# main.net
KiCad netlist of a schematic drawn in Altium Designer
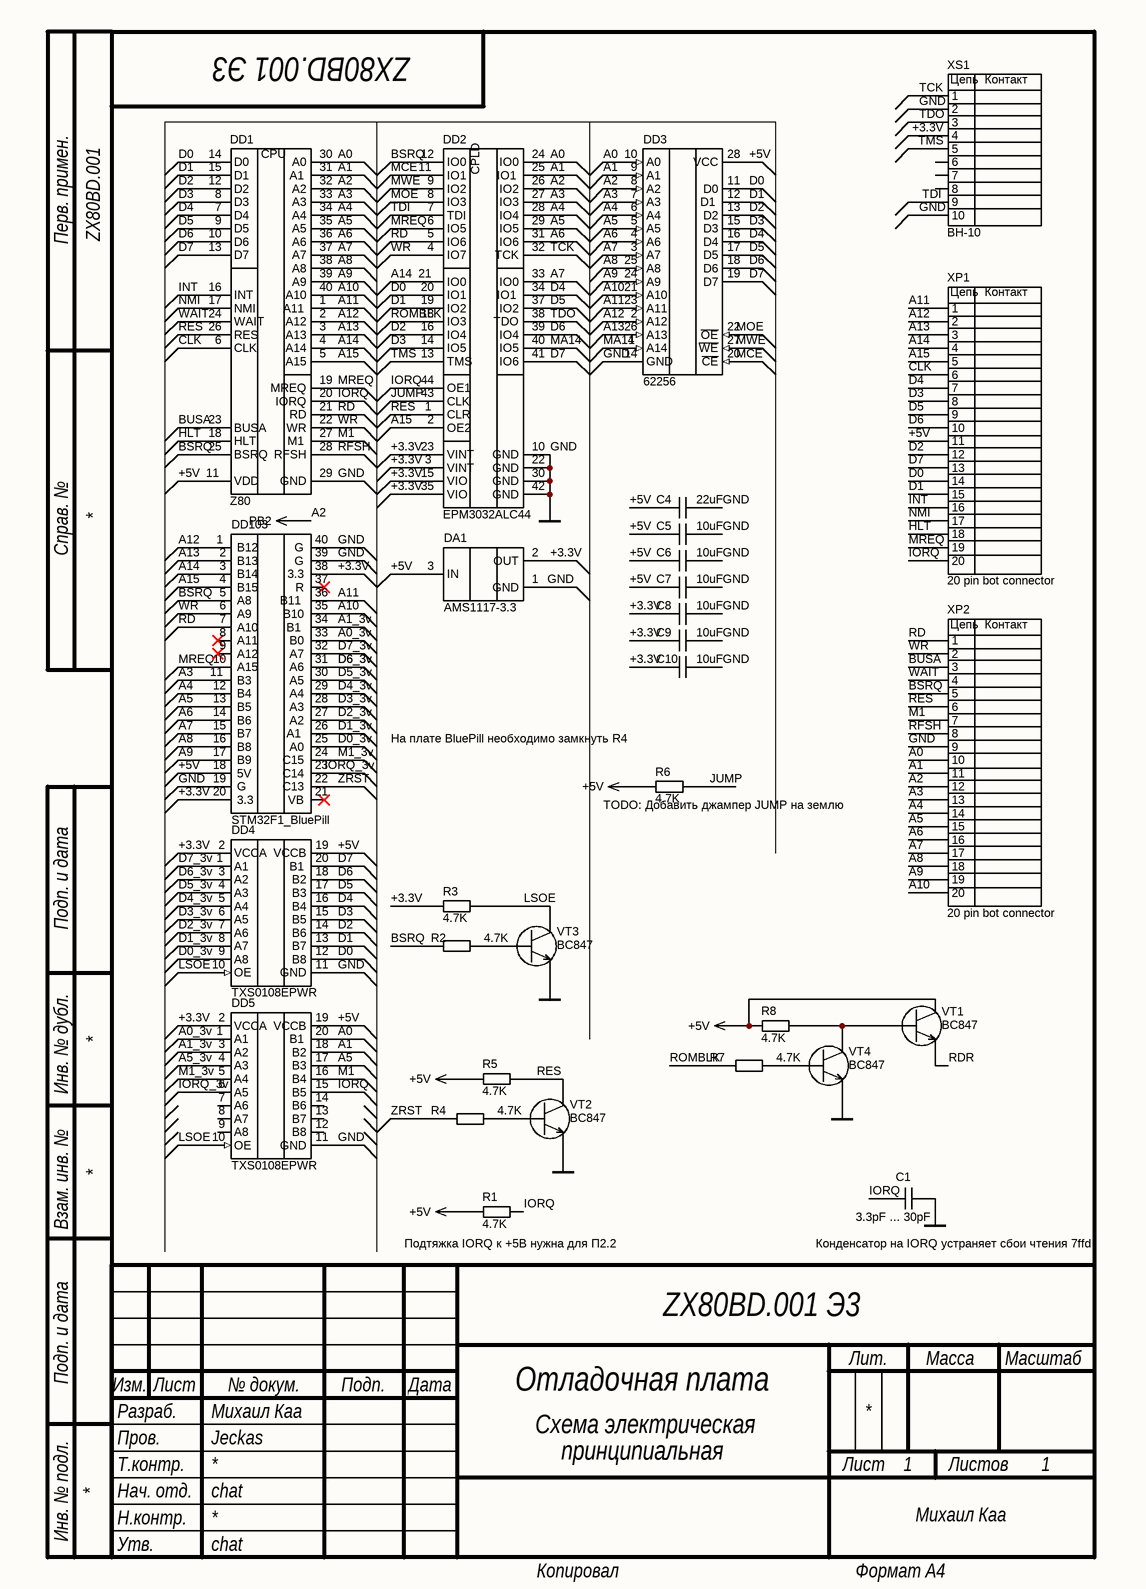
[diagram p0: main.SchDoc]

(export (version "E")
  (design (tool "Eeschema 10.0.6"))
  (components
    (comp (ref "C1")
      (value "3.3pF ... 30pF")
      (footprint "C0805")
      (libsource (lib "Capacitors") (part "CapCer"))
    )
    (comp (ref "C4") (value "22uF") (footprint "С1206") (libsource (lib "Capacitors") (part "CapCer")))
    (comp (ref "C5") (value "10uF") (footprint "C0805") (libsource (lib "Capacitors") (part "CapCer")))
    (comp (ref "C6") (value "10uF") (footprint "C0805") (libsource (lib "Capacitors") (part "CapCer")))
    (comp (ref "C7") (value "10uF") (footprint "C0805") (libsource (lib "Capacitors") (part "CapCer")))
    (comp (ref "C8") (value "10uF") (footprint "C0805") (libsource (lib "Capacitors") (part "CapCer")))
    (comp (ref "C9") (value "10uF") (footprint "C0805") (libsource (lib "Capacitors") (part "CapCer")))
    (comp (ref "C10") (value "10uF") (footprint "C0805") (libsource (lib "Capacitors") (part "CapCer")))
    (comp (ref "DA1")
      (value "AMS1117-3.3")
      (footprint "SOT229P700X180-4N")
      (libsource (lib "LDO") (part "AMS1117-3.3"))
    )
    (comp (ref "DD1")
      (value "Z80")
      (footprint "DIP1540W47P254L5320H635Q40B")
      (libsource (lib "Z80") (part "Z80"))
    )
    (comp (ref "DD2")
      (value "EPM3032ALC44")
      (footprint "PLCC-44-R")
      (description "44-Pin PLCC44")
      (libsource (lib "cpld") (part "EPM3032ALC44"))
    )
    (comp (ref "DD3")
      (value "62256")
      (footprint "DIP28")
      (fields (field (name "MF") "BRADY"))
      (libsource (lib "RAM") (part "62256"))
    )
    (comp (ref "DD4")
      (value "TXS0108EPWR")
      (footprint "SOP65P640X120-20N")
      (description "8-bit bidirectional voltage-level shifter for open-drain and push-pull application")
      (fields (field (name "MF") "Texas Instruments"))
      (libsource (lib "Shifter") (part "TXS0108EPWR"))
    )
    (comp (ref "DD5")
      (value "TXS0108EPWR")
      (footprint "SOP65P640X120-20N")
      (description "8-bit bidirectional voltage-level shifter for open-drain and push-pull application")
      (fields (field (name "MF") "Texas Instruments"))
      (libsource (lib "Shifter") (part "TXS0108EPWR"))
    )
    (comp (ref "DD103")
      (value "STM32F1_BluePill")
      (footprint "PCB-STM32F103")
      (description "STM32F103C8T6")
      (libsource (lib "MCU") (part "STM32F1_BluePill"))
    )
    (comp (ref "R1") (value "4.7K") (footprint "R0805") (libsource (lib "Resistors") (part "Res")))
    (comp (ref "R2") (value "4.7K") (footprint "R0805") (libsource (lib "Resistors") (part "Res")))
    (comp (ref "R3") (value "4.7K") (footprint "R0805") (libsource (lib "Resistors") (part "Res")))
    (comp (ref "R4") (value "4.7K") (footprint "R0805") (libsource (lib "Resistors") (part "Res")))
    (comp (ref "R5") (value "4.7K") (footprint "R0805") (libsource (lib "Resistors") (part "Res")))
    (comp (ref "R6") (value "4.7K") (footprint "R0805") (libsource (lib "Resistors") (part "Res")))
    (comp (ref "R7") (value "4.7K") (footprint "R0805") (libsource (lib "Resistors") (part "Res")))
    (comp (ref "R8") (value "4.7K") (footprint "R0805") (libsource (lib "Resistors") (part "Res")))
    (comp (ref "VT1")
      (value "BC847")
      (footprint "BC847")
      (description "NPN Transistor")
      (libsource (lib "Transistors") (part "BC847"))
    )
    (comp (ref "VT2")
      (value "BC847")
      (footprint "BC847")
      (description "NPN Transistor")
      (libsource (lib "Transistors") (part "BC847"))
    )
    (comp (ref "VT3")
      (value "BC847")
      (footprint "BC847")
      (description "NPN Transistor")
      (libsource (lib "Transistors") (part "BC847"))
    )
    (comp (ref "VT4")
      (value "BC847")
      (footprint "BC847")
      (description "NPN Transistor")
      (libsource (lib "Transistors") (part "BC847"))
    )
    (comp (ref "XP1")
      (value "20 pin bot connector")
      (footprint "20pin header")
      (description "20 Pin 2.54 mm")
      (libsource (lib "Connectors") (part "20 pin bot connector"))
    )
    (comp (ref "XP2")
      (value "20 pin bot connector")
      (footprint "20pin header")
      (description "20 Pin 2.54 mm")
      (libsource (lib "Connectors") (part "20 pin bot connector"))
    )
    (comp (ref "XS1")
      (value "BH-10")
      (footprint "BH-10")
      (description "10 Position Total Dual Row 2.54 mm Pitch Straight Male Shrouded Box Header")
      (fields (field (name "MF") "Sullins Connector") (field (name "MP") "SBH11-PBPC-D05-ST-BK"))
      (libsource (lib "Connectors") (part "BH-10"))
    )
  )
  (nets
    (net (code "1") (name "+5V") (class "Default")
      (node (ref "C4") (pin "1") (pinfunction "1_1") (pintype "passive"))
      (node (ref "C5") (pin "1") (pinfunction "1_1") (pintype "passive"))
      (node (ref "C6") (pin "1") (pinfunction "1_1") (pintype "passive"))
      (node (ref "C7") (pin "1") (pinfunction "1_1") (pintype "passive"))
      (node (ref "DA1") (pin "3") (pinfunction "IN_3") (pintype "passive"))
      (node (ref "DD1") (pin "11") (pinfunction "VDD_11") (pintype "passive"))
      (node (ref "DD103") (pin "18") (pinfunction "5V_18") (pintype "passive"))
      (node (ref "DD3") (pin "28") (pinfunction "VCC_28") (pintype "power_in"))
      (node (ref "DD4") (pin "19") (pinfunction "VCCB_19") (pintype "power_in"))
      (node (ref "DD5") (pin "19") (pinfunction "VCCB_19") (pintype "power_in"))
      (node (ref "R1") (pin "2") (pinfunction "2_2") (pintype "passive"))
      (node (ref "R5") (pin "2") (pinfunction "2_2") (pintype "passive"))
      (node (ref "R6") (pin "2") (pinfunction "2_2") (pintype "passive"))
      (node (ref "R8") (pin "2") (pinfunction "2_2") (pintype "passive"))
      (node (ref "VT1") (pin "3") (pinfunction "C_3") (pintype "power_in"))
      (node (ref "XP1") (pin "11") (pinfunction "11_11") (pintype "passive"))
    )
    (net (code "2") (name "/+3.3V") (class "Default")
      (node (ref "C10") (pin "1") (pinfunction "1_1") (pintype "passive"))
      (node (ref "C8") (pin "1") (pinfunction "1_1") (pintype "passive"))
      (node (ref "C9") (pin "1") (pinfunction "1_1") (pintype "passive"))
      (node (ref "DA1") (pin "2") (pinfunction "OUT_2") (pintype "passive"))
      (node (ref "DD103") (pin "20") (pinfunction "3.3_20") (pintype "passive"))
      (node (ref "DD103") (pin "38") (pinfunction "3.3_38") (pintype "passive"))
      (node (ref "DD2") (pin "15") (pinfunction "VIO_15") (pintype "passive"))
      (node (ref "DD2") (pin "23") (pinfunction "VINT_23") (pintype "passive"))
      (node (ref "DD2") (pin "3") (pinfunction "VINT_3") (pintype "passive"))
      (node (ref "DD2") (pin "35") (pinfunction "VIO_35") (pintype "passive"))
      (node (ref "DD4") (pin "2") (pinfunction "VCCA_2") (pintype "power_in"))
      (node (ref "DD5") (pin "2") (pinfunction "VCCA_2") (pintype "power_in"))
      (node (ref "R3") (pin "2") (pinfunction "2_2") (pintype "passive"))
      (node (ref "XS1") (pin "4") (pinfunction "4_4") (pintype "passive"))
    )
    (net (code "3") (name "/A0") (class "Default")
      (node (ref "DD1") (pin "30") (pinfunction "A0_30") (pintype "passive"))
      (node (ref "DD2") (pin "24") (pinfunction "IO0_24") (pintype "passive"))
      (node (ref "DD3") (pin "10") (pinfunction "A0_10") (pintype "input"))
      (node (ref "DD5") (pin "20") (pinfunction "B1_20") (pintype "bidirectional"))
      (node (ref "XP2") (pin "10") (pinfunction "10_10") (pintype "passive"))
    )
    (net (code "4") (name "/A0_3v") (class "Default")
      (node (ref "DD103") (pin "33") (pinfunction "B0_33") (pintype "passive"))
      (node (ref "DD5") (pin "1") (pinfunction "A1_1") (pintype "bidirectional"))
    )
    (net (code "5") (name "/A1") (class "Default")
      (node (ref "DD1") (pin "31") (pinfunction "A1_31") (pintype "passive"))
      (node (ref "DD2") (pin "25") (pinfunction "IO1_25") (pintype "passive"))
      (node (ref "DD3") (pin "9") (pinfunction "A1_9") (pintype "input"))
      (node (ref "DD5") (pin "18") (pinfunction "B2_18") (pintype "bidirectional"))
      (node (ref "XP2") (pin "11") (pinfunction "11_11") (pintype "passive"))
    )
    (net (code "6") (name "/A1_3v") (class "Default")
      (node (ref "DD103") (pin "34") (pinfunction "B1_34") (pintype "passive"))
      (node (ref "DD5") (pin "3") (pinfunction "A2_3") (pintype "bidirectional"))
    )
    (net (code "7") (name "/A3") (class "Default")
      (node (ref "DD1") (pin "33") (pinfunction "A3_33") (pintype "passive"))
      (node (ref "DD103") (pin "11") (pinfunction "B3_11") (pintype "passive"))
      (node (ref "DD2") (pin "27") (pinfunction "IO3_27") (pintype "passive"))
      (node (ref "DD3") (pin "7") (pinfunction "A3_7") (pintype "input"))
      (node (ref "XP2") (pin "13") (pinfunction "13_13") (pintype "passive"))
    )
    (net (code "8") (name "/A4") (class "Default")
      (node (ref "DD1") (pin "34") (pinfunction "A4_34") (pintype "passive"))
      (node (ref "DD103") (pin "12") (pinfunction "B4_12") (pintype "passive"))
      (node (ref "DD2") (pin "28") (pinfunction "IO4_28") (pintype "passive"))
      (node (ref "DD3") (pin "6") (pinfunction "A4_6") (pintype "input"))
      (node (ref "XP2") (pin "14") (pinfunction "14_14") (pintype "passive"))
    )
    (net (code "9") (name "/A5") (class "Default")
      (node (ref "DD1") (pin "35") (pinfunction "A5_35") (pintype "passive"))
      (node (ref "DD103") (pin "13") (pinfunction "B5_13") (pintype "passive"))
      (node (ref "DD2") (pin "29") (pinfunction "IO5_29") (pintype "passive"))
      (node (ref "DD3") (pin "5") (pinfunction "A5_5") (pintype "input"))
      (node (ref "DD5") (pin "17") (pinfunction "B3_17") (pintype "bidirectional"))
      (node (ref "XP2") (pin "15") (pinfunction "15_15") (pintype "passive"))
    )
    (net (code "10") (name "/A5_3v") (class "Default")
      (node (ref "DD5") (pin "4") (pinfunction "A3_4") (pintype "bidirectional"))
    )
    (net (code "11") (name "/A6") (class "Default")
      (node (ref "DD1") (pin "36") (pinfunction "A6_36") (pintype "passive"))
      (node (ref "DD103") (pin "14") (pinfunction "B6_14") (pintype "passive"))
      (node (ref "DD2") (pin "31") (pinfunction "IO6_31") (pintype "passive"))
      (node (ref "DD3") (pin "4") (pinfunction "A6_4") (pintype "input"))
      (node (ref "XP2") (pin "16") (pinfunction "16_16") (pintype "passive"))
    )
    (net (code "12") (name "/A7") (class "Default")
      (node (ref "DD1") (pin "37") (pinfunction "A7_37") (pintype "passive"))
      (node (ref "DD103") (pin "15") (pinfunction "B7_15") (pintype "passive"))
      (node (ref "DD2") (pin "33") (pinfunction "IO0_33") (pintype "passive"))
      (node (ref "DD3") (pin "3") (pinfunction "A7_3") (pintype "input"))
      (node (ref "XP2") (pin "17") (pinfunction "17_17") (pintype "passive"))
    )
    (net (code "13") (name "/A8") (class "Default")
      (node (ref "DD1") (pin "38") (pinfunction "A8_38") (pintype "passive"))
      (node (ref "DD103") (pin "16") (pinfunction "B8_16") (pintype "passive"))
      (node (ref "DD3") (pin "25") (pinfunction "A8_25") (pintype "input"))
      (node (ref "XP2") (pin "18") (pinfunction "18_18") (pintype "passive"))
    )
    (net (code "14") (name "/A9") (class "Default")
      (node (ref "DD1") (pin "39") (pinfunction "A9_39") (pintype "passive"))
      (node (ref "DD103") (pin "17") (pinfunction "B9_17") (pintype "passive"))
      (node (ref "DD3") (pin "24") (pinfunction "A9_24") (pintype "input"))
      (node (ref "XP2") (pin "19") (pinfunction "19_19") (pintype "passive"))
    )
    (net (code "15") (name "/A10") (class "Default")
      (node (ref "DD1") (pin "40") (pinfunction "A10_40") (pintype "passive"))
      (node (ref "DD103") (pin "35") (pinfunction "B10_35") (pintype "passive"))
      (node (ref "DD3") (pin "21") (pinfunction "A10_21") (pintype "input"))
      (node (ref "XP2") (pin "20") (pinfunction "20_20") (pintype "passive"))
    )
    (net (code "16") (name "/A11") (class "Default")
      (node (ref "DD1") (pin "1") (pinfunction "A11_1") (pintype "passive"))
      (node (ref "DD103") (pin "36") (pinfunction "B11_36") (pintype "passive"))
      (node (ref "DD3") (pin "23") (pinfunction "A11_23") (pintype "input"))
      (node (ref "XP1") (pin "1") (pinfunction "1_1") (pintype "passive"))
    )
    (net (code "17") (name "/A12") (class "Default")
      (node (ref "DD1") (pin "2") (pinfunction "A12_2") (pintype "passive"))
      (node (ref "DD103") (pin "1") (pinfunction "B12_1") (pintype "passive"))
      (node (ref "DD3") (pin "2") (pinfunction "A12_2") (pintype "input"))
      (node (ref "XP1") (pin "2") (pinfunction "2_2") (pintype "passive"))
    )
    (net (code "18") (name "/A13") (class "Default")
      (node (ref "DD1") (pin "3") (pinfunction "A13_3") (pintype "passive"))
      (node (ref "DD103") (pin "2") (pinfunction "B13_2") (pintype "passive"))
      (node (ref "DD3") (pin "26") (pinfunction "A13_26") (pintype "input"))
      (node (ref "XP1") (pin "3") (pinfunction "3_3") (pintype "passive"))
    )
    (net (code "19") (name "/A14") (class "Default")
      (node (ref "DD1") (pin "4") (pinfunction "A14_4") (pintype "passive"))
      (node (ref "DD103") (pin "3") (pinfunction "B14_3") (pintype "passive"))
      (node (ref "DD2") (pin "21") (pinfunction "IO0_21") (pintype "passive"))
      (node (ref "XP1") (pin "4") (pinfunction "4_4") (pintype "passive"))
    )
    (net (code "20") (name "/A15") (class "Default")
      (node (ref "DD1") (pin "5") (pinfunction "A15_5") (pintype "passive"))
      (node (ref "DD103") (pin "4") (pinfunction "B15_4") (pintype "passive"))
      (node (ref "DD2") (pin "2") (pinfunction "OE2_2") (pintype "passive"))
      (node (ref "XP1") (pin "5") (pinfunction "5_5") (pintype "passive"))
    )
    (net (code "21") (name "/BSRQ") (class "Default")
      (node (ref "DD1") (pin "25") (pinfunction "BSRQ_25") (pintype "passive"))
      (node (ref "DD103") (pin "5") (pinfunction "A8_5") (pintype "passive"))
      (node (ref "DD2") (pin "12") (pinfunction "IO0_12") (pintype "passive"))
      (node (ref "R2") (pin "1") (pinfunction "1_1") (pintype "passive"))
      (node (ref "XP2") (pin "5") (pinfunction "5_5") (pintype "passive"))
    )
    (net (code "22") (name "/BUSA") (class "Default")
      (node (ref "DD1") (pin "23") (pinfunction "BUSA_23") (pintype "passive"))
      (node (ref "XP2") (pin "3") (pinfunction "3_3") (pintype "passive"))
    )
    (net (code "23") (name "/CLK") (class "Default")
      (node (ref "DD1") (pin "6") (pinfunction "CLK_6") (pintype "passive"))
      (node (ref "XP1") (pin "6") (pinfunction "6_6") (pintype "passive"))
    )
    (net (code "24") (name "/D0") (class "Default")
      (node (ref "DD1") (pin "14") (pinfunction "D0_14") (pintype "passive"))
      (node (ref "DD2") (pin "20") (pinfunction "IO1_20") (pintype "passive"))
      (node (ref "DD3") (pin "11") (pinfunction "D0_11") (pintype "bidirectional"))
      (node (ref "DD4") (pin "12") (pinfunction "B8_12") (pintype "bidirectional"))
      (node (ref "XP1") (pin "14") (pinfunction "14_14") (pintype "passive"))
    )
    (net (code "25") (name "/D0_3v") (class "Default")
      (node (ref "DD103") (pin "25") (pinfunction "A0_25") (pintype "passive"))
      (node (ref "DD4") (pin "9") (pinfunction "A8_9") (pintype "bidirectional"))
    )
    (net (code "26") (name "/D1") (class "Default")
      (node (ref "DD1") (pin "15") (pinfunction "D1_15") (pintype "passive"))
      (node (ref "DD2") (pin "19") (pinfunction "IO2_19") (pintype "passive"))
      (node (ref "DD3") (pin "12") (pinfunction "D1_12") (pintype "bidirectional"))
      (node (ref "DD4") (pin "13") (pinfunction "B7_13") (pintype "bidirectional"))
      (node (ref "XP1") (pin "15") (pinfunction "15_15") (pintype "passive"))
    )
    (net (code "27") (name "/D1_3v") (class "Default")
      (node (ref "DD103") (pin "26") (pinfunction "A1_26") (pintype "passive"))
      (node (ref "DD4") (pin "8") (pinfunction "A7_8") (pintype "bidirectional"))
    )
    (net (code "28") (name "/D2") (class "Default")
      (node (ref "DD1") (pin "12") (pinfunction "D2_12") (pintype "passive"))
      (node (ref "DD2") (pin "16") (pinfunction "IO4_16") (pintype "passive"))
      (node (ref "DD3") (pin "13") (pinfunction "D2_13") (pintype "bidirectional"))
      (node (ref "DD4") (pin "14") (pinfunction "B6_14") (pintype "bidirectional"))
      (node (ref "XP1") (pin "12") (pinfunction "12_12") (pintype "passive"))
    )
    (net (code "29") (name "/D2_3v") (class "Default")
      (node (ref "DD103") (pin "27") (pinfunction "A2_27") (pintype "passive"))
      (node (ref "DD4") (pin "7") (pinfunction "A6_7") (pintype "bidirectional"))
    )
    (net (code "30") (name "/D3") (class "Default")
      (node (ref "DD1") (pin "8") (pinfunction "D3_8") (pintype "passive"))
      (node (ref "DD2") (pin "14") (pinfunction "IO5_14") (pintype "passive"))
      (node (ref "DD3") (pin "15") (pinfunction "D3_15") (pintype "bidirectional"))
      (node (ref "DD4") (pin "15") (pinfunction "B5_15") (pintype "bidirectional"))
      (node (ref "XP1") (pin "8") (pinfunction "8_8") (pintype "passive"))
    )
    (net (code "31") (name "/D3_3v") (class "Default")
      (node (ref "DD103") (pin "28") (pinfunction "A3_28") (pintype "passive"))
      (node (ref "DD4") (pin "6") (pinfunction "A5_6") (pintype "bidirectional"))
    )
    (net (code "32") (name "/D4") (class "Default")
      (node (ref "DD1") (pin "7") (pinfunction "D4_7") (pintype "passive"))
      (node (ref "DD2") (pin "34") (pinfunction "IO1_34") (pintype "passive"))
      (node (ref "DD3") (pin "16") (pinfunction "D4_16") (pintype "bidirectional"))
      (node (ref "DD4") (pin "16") (pinfunction "B4_16") (pintype "bidirectional"))
      (node (ref "XP1") (pin "7") (pinfunction "7_7") (pintype "passive"))
    )
    (net (code "33") (name "/D4_3v") (class "Default")
      (node (ref "DD103") (pin "29") (pinfunction "A4_29") (pintype "passive"))
      (node (ref "DD4") (pin "5") (pinfunction "A4_5") (pintype "bidirectional"))
    )
    (net (code "34") (name "/D5") (class "Default")
      (node (ref "DD1") (pin "9") (pinfunction "D5_9") (pintype "passive"))
      (node (ref "DD2") (pin "37") (pinfunction "IO2_37") (pintype "passive"))
      (node (ref "DD3") (pin "17") (pinfunction "D5_17") (pintype "bidirectional"))
      (node (ref "DD4") (pin "17") (pinfunction "B3_17") (pintype "bidirectional"))
      (node (ref "XP1") (pin "9") (pinfunction "9_9") (pintype "passive"))
    )
    (net (code "35") (name "/D5_3v") (class "Default")
      (node (ref "DD103") (pin "30") (pinfunction "A5_30") (pintype "passive"))
      (node (ref "DD4") (pin "4") (pinfunction "A3_4") (pintype "bidirectional"))
    )
    (net (code "36") (name "/D6") (class "Default")
      (node (ref "DD1") (pin "10") (pinfunction "D6_10") (pintype "passive"))
      (node (ref "DD2") (pin "39") (pinfunction "IO4_39") (pintype "passive"))
      (node (ref "DD3") (pin "18") (pinfunction "D6_18") (pintype "bidirectional"))
      (node (ref "DD4") (pin "18") (pinfunction "B2_18") (pintype "bidirectional"))
      (node (ref "XP1") (pin "10") (pinfunction "10_10") (pintype "passive"))
    )
    (net (code "37") (name "/D6_3v") (class "Default")
      (node (ref "DD103") (pin "31") (pinfunction "A6_31") (pintype "passive"))
      (node (ref "DD4") (pin "3") (pinfunction "A2_3") (pintype "bidirectional"))
    )
    (net (code "38") (name "/D7") (class "Default")
      (node (ref "DD1") (pin "13") (pinfunction "D7_13") (pintype "passive"))
      (node (ref "DD2") (pin "41") (pinfunction "IO6_41") (pintype "passive"))
      (node (ref "DD3") (pin "19") (pinfunction "D7_19") (pintype "bidirectional"))
      (node (ref "DD4") (pin "20") (pinfunction "B1_20") (pintype "bidirectional"))
      (node (ref "XP1") (pin "13") (pinfunction "13_13") (pintype "passive"))
    )
    (net (code "39") (name "/D7_3v") (class "Default")
      (node (ref "DD103") (pin "32") (pinfunction "A7_32") (pintype "passive"))
      (node (ref "DD4") (pin "1") (pinfunction "A1_1") (pintype "bidirectional"))
    )
    (net (code "40") (name "/HLT") (class "Default")
      (node (ref "DD1") (pin "18") (pinfunction "HLT_18") (pintype "passive"))
      (node (ref "XP1") (pin "18") (pinfunction "18_18") (pintype "passive"))
    )
    (net (code "41") (name "/INT") (class "Default")
      (node (ref "DD1") (pin "16") (pinfunction "INT_16") (pintype "passive"))
      (node (ref "XP1") (pin "16") (pinfunction "16_16") (pintype "passive"))
    )
    (net (code "42") (name "/IORQ") (class "Default")
      (node (ref "C1") (pin "1") (pinfunction "1_1") (pintype "passive"))
      (node (ref "DD1") (pin "20") (pinfunction "IORQ_20") (pintype "passive"))
      (node (ref "DD2") (pin "44") (pinfunction "OE1_44") (pintype "passive"))
      (node (ref "DD5") (pin "15") (pinfunction "B5_15") (pintype "bidirectional"))
      (node (ref "R1") (pin "1") (pinfunction "1_1") (pintype "passive"))
      (node (ref "XP1") (pin "20") (pinfunction "20_20") (pintype "passive"))
    )
    (net (code "43") (name "/IORQ_3v") (class "Default")
      (node (ref "DD103") (pin "23") (pinfunction "C14_23") (pintype "passive"))
      (node (ref "DD5") (pin "6") (pinfunction "A5_6") (pintype "bidirectional"))
    )
    (net (code "44") (name "/JUMP") (class "Default")
      (node (ref "DD2") (pin "43") (pinfunction "CLK_43") (pintype "passive"))
      (node (ref "R6") (pin "1") (pinfunction "1_1") (pintype "passive"))
    )
    (net (code "45") (name "/LSOE") (class "Default")
      (node (ref "DD4") (pin "10") (pinfunction "OE_10") (pintype "input"))
      (node (ref "DD5") (pin "10") (pinfunction "OE_10") (pintype "input"))
      (node (ref "R3") (pin "1") (pinfunction "1_1") (pintype "passive"))
      (node (ref "VT3") (pin "3") (pinfunction "C_3") (pintype "power_in"))
    )
    (net (code "46") (name "/M1") (class "Default")
      (node (ref "DD1") (pin "27") (pinfunction "M1_27") (pintype "passive"))
      (node (ref "DD5") (pin "16") (pinfunction "B4_16") (pintype "bidirectional"))
      (node (ref "XP2") (pin "7") (pinfunction "7_7") (pintype "passive"))
    )
    (net (code "47") (name "/M1_3v") (class "Default")
      (node (ref "DD103") (pin "24") (pinfunction "C15_24") (pintype "passive"))
      (node (ref "DD5") (pin "5") (pinfunction "A4_5") (pintype "bidirectional"))
    )
    (net (code "48") (name "/MA14") (class "Default")
      (node (ref "DD2") (pin "40") (pinfunction "IO5_40") (pintype "passive"))
      (node (ref "DD3") (pin "1") (pinfunction "A14_1") (pintype "input"))
    )
    (net (code "49") (name "/MCE") (class "Default")
      (node (ref "DD2") (pin "11") (pinfunction "IO1_11") (pintype "passive"))
      (node (ref "DD3") (pin "20") (pinfunction "~{CE}_20") (pintype "input"))
    )
    (net (code "50") (name "/MOE") (class "Default")
      (node (ref "DD2") (pin "8") (pinfunction "IO3_8") (pintype "passive"))
      (node (ref "DD3") (pin "22") (pinfunction "~{OE}_22") (pintype "input"))
    )
    (net (code "51") (name "/MREQ") (class "Default")
      (node (ref "DD1") (pin "19") (pinfunction "MREQ_19") (pintype "passive"))
      (node (ref "DD103") (pin "10") (pinfunction "A15_10") (pintype "passive"))
      (node (ref "DD2") (pin "6") (pinfunction "IO5_6") (pintype "passive"))
      (node (ref "XP1") (pin "19") (pinfunction "19_19") (pintype "passive"))
    )
    (net (code "52") (name "/MWE") (class "Default")
      (node (ref "DD2") (pin "9") (pinfunction "IO2_9") (pintype "passive"))
      (node (ref "DD3") (pin "27") (pinfunction "~{WE}_27") (pintype "input"))
    )
    (net (code "53") (name "/NMI") (class "Default")
      (node (ref "DD1") (pin "17") (pinfunction "NMI_17") (pintype "passive"))
      (node (ref "XP1") (pin "17") (pinfunction "17_17") (pintype "passive"))
    )
    (net (code "54") (name "/RD") (class "Default")
      (node (ref "DD1") (pin "21") (pinfunction "RD_21") (pintype "passive"))
      (node (ref "DD103") (pin "7") (pinfunction "A10_7") (pintype "passive"))
      (node (ref "DD2") (pin "5") (pinfunction "IO6_5") (pintype "passive"))
      (node (ref "XP2") (pin "1") (pinfunction "1_1") (pintype "passive"))
    )
    (net (code "55") (name "/RDR") (class "Default")
      (node (ref "VT1") (pin "2") (pinfunction "E_2") (pintype "power_in"))
    )
    (net (code "56") (name "/RES") (class "Default")
      (node (ref "DD1") (pin "26") (pinfunction "RES_26") (pintype "passive"))
      (node (ref "DD2") (pin "1") (pinfunction "CLR_1") (pintype "passive"))
      (node (ref "R5") (pin "1") (pinfunction "1_1") (pintype "passive"))
      (node (ref "VT2") (pin "3") (pinfunction "C_3") (pintype "power_in"))
      (node (ref "XP2") (pin "6") (pinfunction "6_6") (pintype "passive"))
    )
    (net (code "57") (name "/RFSH") (class "Default")
      (node (ref "DD1") (pin "28") (pinfunction "RFSH_28") (pintype "passive"))
      (node (ref "XP2") (pin "8") (pinfunction "8_8") (pintype "passive"))
    )
    (net (code "58") (name "/ROMBLK") (class "Default")
      (node (ref "DD2") (pin "18") (pinfunction "IO3_18") (pintype "passive"))
      (node (ref "R7") (pin "1") (pinfunction "1_1") (pintype "passive"))
    )
    (net (code "59") (name "/TCK") (class "Default")
      (node (ref "DD2") (pin "32") (pinfunction "TCK_32") (pintype "passive"))
      (node (ref "XS1") (pin "1") (pinfunction "1_1") (pintype "passive"))
    )
    (net (code "60") (name "/TDI") (class "Default")
      (node (ref "DD2") (pin "7") (pinfunction "TDI_7") (pintype "passive"))
      (node (ref "XS1") (pin "9") (pinfunction "9_9") (pintype "passive"))
    )
    (net (code "61") (name "/TDO") (class "Default")
      (node (ref "DD2") (pin "38") (pinfunction "TDO_38") (pintype "passive"))
      (node (ref "XS1") (pin "3") (pinfunction "3_3") (pintype "passive"))
    )
    (net (code "62") (name "/TMS") (class "Default")
      (node (ref "DD2") (pin "13") (pinfunction "TMS_13") (pintype "passive"))
      (node (ref "XS1") (pin "5") (pinfunction "5_5") (pintype "passive"))
    )
    (net (code "63") (name "/WAIT") (class "Default")
      (node (ref "DD1") (pin "24") (pinfunction "WAIT_24") (pintype "passive"))
      (node (ref "XP2") (pin "4") (pinfunction "4_4") (pintype "passive"))
    )
    (net (code "64") (name "/WR") (class "Default")
      (node (ref "DD1") (pin "22") (pinfunction "WR_22") (pintype "passive"))
      (node (ref "DD103") (pin "6") (pinfunction "A9_6") (pintype "passive"))
      (node (ref "DD2") (pin "4") (pinfunction "IO7_4") (pintype "passive"))
      (node (ref "XP2") (pin "2") (pinfunction "2_2") (pintype "passive"))
    )
    (net (code "65") (name "/ZRST") (class "Default")
      (node (ref "DD103") (pin "22") (pinfunction "C13_22") (pintype "passive"))
      (node (ref "R4") (pin "1") (pinfunction "1_1") (pintype "passive"))
    )
    (net (code "66") (name "GND") (class "Default")
      (node (ref "C1") (pin "2") (pinfunction "2_2") (pintype "passive"))
      (node (ref "C10") (pin "2") (pinfunction "2_2") (pintype "passive"))
      (node (ref "C4") (pin "2") (pinfunction "2_2") (pintype "passive"))
      (node (ref "C5") (pin "2") (pinfunction "2_2") (pintype "passive"))
      (node (ref "C6") (pin "2") (pinfunction "2_2") (pintype "passive"))
      (node (ref "C7") (pin "2") (pinfunction "2_2") (pintype "passive"))
      (node (ref "C8") (pin "2") (pinfunction "2_2") (pintype "passive"))
      (node (ref "C9") (pin "2") (pinfunction "2_2") (pintype "passive"))
      (node (ref "DA1") (pin "1") (pinfunction "GND_1") (pintype "passive"))
      (node (ref "DD1") (pin "29") (pinfunction "GND_29") (pintype "passive"))
      (node (ref "DD103") (pin "19") (pinfunction "G_19") (pintype "passive"))
      (node (ref "DD103") (pin "39") (pinfunction "G_39") (pintype "passive"))
      (node (ref "DD103") (pin "40") (pinfunction "G_40") (pintype "passive"))
      (node (ref "DD2") (pin "10") (pinfunction "GND_10") (pintype "passive"))
      (node (ref "DD2") (pin "22") (pinfunction "GND_22") (pintype "passive"))
      (node (ref "DD2") (pin "30") (pinfunction "GND_30") (pintype "passive"))
      (node (ref "DD2") (pin "42") (pinfunction "GND_42") (pintype "passive"))
      (node (ref "DD3") (pin "14") (pinfunction "GND_14") (pintype "power_in"))
      (node (ref "DD4") (pin "11") (pinfunction "GND_11") (pintype "power_in"))
      (node (ref "DD5") (pin "11") (pinfunction "GND_11") (pintype "power_in"))
      (node (ref "VT2") (pin "2") (pinfunction "E_2") (pintype "power_in"))
      (node (ref "VT3") (pin "2") (pinfunction "E_2") (pintype "power_in"))
      (node (ref "VT4") (pin "2") (pinfunction "E_2") (pintype "power_in"))
      (node (ref "XP2") (pin "9") (pinfunction "9_9") (pintype "passive"))
      (node (ref "XS1") (pin "10") (pinfunction "10_10") (pintype "passive"))
      (node (ref "XS1") (pin "2") (pinfunction "2_2") (pintype "passive"))
    )
    (net (code "67") (name "Net-(VT1-B)") (class "Default")
      (node (ref "R8") (pin "1") (pinfunction "1_1") (pintype "passive"))
      (node (ref "VT1") (pin "1") (pinfunction "B_1") (pintype "power_in"))
      (node (ref "VT4") (pin "3") (pinfunction "C_3") (pintype "power_in"))
    )
    (net (code "68") (name "Net-(VT2-B)") (class "Default")
      (node (ref "R4") (pin "2") (pinfunction "2_2") (pintype "passive"))
      (node (ref "VT2") (pin "1") (pinfunction "B_1") (pintype "power_in"))
    )
    (net (code "69") (name "Net-(VT3-B)") (class "Default")
      (node (ref "R2") (pin "2") (pinfunction "2_2") (pintype "passive"))
      (node (ref "VT3") (pin "1") (pinfunction "B_1") (pintype "power_in"))
    )
    (net (code "70") (name "Net-(VT4-B)") (class "Default")
      (node (ref "R7") (pin "2") (pinfunction "2_2") (pintype "passive"))
      (node (ref "VT4") (pin "1") (pinfunction "B_1") (pintype "power_in"))
    )
    (net (code "71") (name "PB2") (class "Default")
      (node (ref "DD1") (pin "32") (pinfunction "A2_32") (pintype "passive"))
      (node (ref "DD2") (pin "26") (pinfunction "IO2_26") (pintype "passive"))
      (node (ref "DD3") (pin "8") (pinfunction "A2_8") (pintype "input"))
      (node (ref "XP2") (pin "12") (pinfunction "12_12") (pintype "passive"))
    )
    (net (code "72") (name "unconnected-(DD5-A6-Pad7)") (class "Default")
      (node (ref "DD5") (pin "7") (pinfunction "A6_7") (pintype "bidirectional"))
    )
    (net (code "73") (name "unconnected-(DD5-A7-Pad8)") (class "Default")
      (node (ref "DD5") (pin "8") (pinfunction "A7_8") (pintype "bidirectional"))
    )
    (net (code "74") (name "unconnected-(DD5-A8-Pad9)") (class "Default")
      (node (ref "DD5") (pin "9") (pinfunction "A8_9") (pintype "bidirectional"))
    )
    (net (code "75") (name "unconnected-(DD5-B6-Pad14)") (class "Default")
      (node (ref "DD5") (pin "14") (pinfunction "B6_14") (pintype "bidirectional"))
    )
    (net (code "76") (name "unconnected-(DD5-B7-Pad13)") (class "Default")
      (node (ref "DD5") (pin "13") (pinfunction "B7_13") (pintype "bidirectional"))
    )
    (net (code "77") (name "unconnected-(DD5-B8-Pad12)") (class "Default")
      (node (ref "DD5") (pin "12") (pinfunction "B8_12") (pintype "bidirectional"))
    )
    (net (code "78") (name "unconnected-(DD103-A11-Pad8)") (class "Default")
      (node (ref "DD103") (pin "8") (pinfunction "A11_8") (pintype "passive+no_connect"))
    )
    (net (code "79") (name "unconnected-(DD103-A12-Pad9)") (class "Default")
      (node (ref "DD103") (pin "9") (pinfunction "A12_9") (pintype "passive+no_connect"))
    )
    (net (code "80") (name "unconnected-(DD103-R-Pad37)") (class "Default")
      (node (ref "DD103") (pin "37") (pinfunction "R_37") (pintype "passive+no_connect"))
    )
    (net (code "81") (name "unconnected-(DD103-VB-Pad21)") (class "Default")
      (node (ref "DD103") (pin "21") (pinfunction "VB_21") (pintype "passive+no_connect"))
    )
    (net (code "82") (name "unconnected-(XS1-Pad6)") (class "Default")
      (node (ref "XS1") (pin "6") (pinfunction "6_6") (pintype "passive"))
    )
    (net (code "83") (name "unconnected-(XS1-Pad7)") (class "Default")
      (node (ref "XS1") (pin "7") (pinfunction "7_7") (pintype "passive"))
    )
    (net (code "84") (name "unconnected-(XS1-Pad8)") (class "Default")
      (node (ref "XS1") (pin "8") (pinfunction "8_8") (pintype "passive"))
    )
  )
)
